# Sheet1.net
KiCad netlist of a schematic drawn in Altium Designer
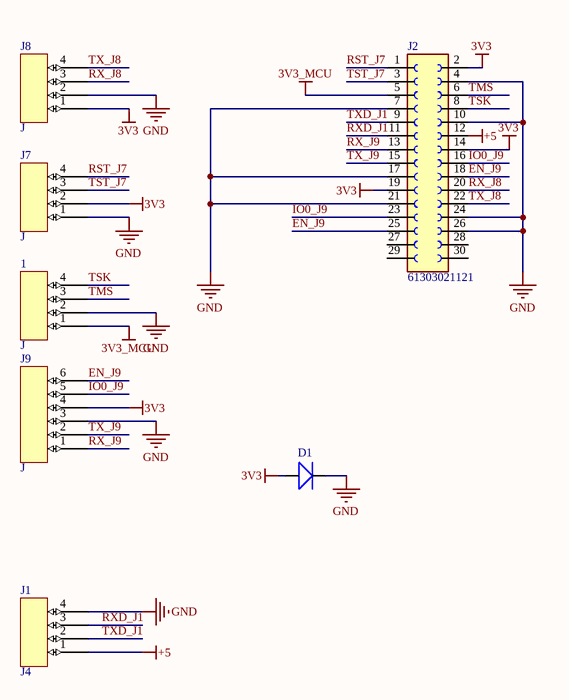
[diagram p0: Sheet1.SchDoc]

(export (version "E")
  (design (tool "Eeschema 10.0.6"))
  (components
    (comp (ref "1") (value "J") (footprint "J4") (libsource (lib "Schlib2") (part "J4")))
    (comp (ref "D1")
      (value "SMD-DIODE-SWITCHING-75V-150MA(D1206)")
      (footprint "LED-1206")
      (description "304040005")
      (fields (field (name "MF") "{'manufacturer': u'Bourns'}"))
      (libsource (lib "CD1206-S01575") (part "SMD-DIODE-SWITCHING-75V-150MA(D1206)"))
    )
    (comp (ref "J1") (value "J4") (footprint "J4") (libsource (lib "Schlib2") (part "J4")))
    (comp (ref "J2")
      (value "61303021121")
      (footprint "61303021121:61303021121")
      (fields (field (name "MF") "{'manufacturer': u'Wurth Elektronik'}"))
      (libsource (lib "*") (part "61303021121"))
    )
    (comp (ref "J7") (value "J") (footprint "J4") (libsource (lib "Schlib2") (part "J4")))
    (comp (ref "J8") (value "J") (footprint "J4") (libsource (lib "Schlib2") (part "J4")))
    (comp (ref "J9") (value "J") (footprint "J6") (libsource (lib "Schlib1") (part "J6")))
  )
  (nets
    (net (code "1") (name "+5") (class "Default")
      (node (ref "J1") (pin "1") (pintype "bidirectional"))
      (node (ref "J2") (pin "12") (pinfunction "25_12") (pintype "passive"))
    )
    (net (code "2") (name "/EN_J9") (class "Default")
      (node (ref "J2") (pin "18") (pinfunction "22_18") (pintype "passive"))
      (node (ref "J2") (pin "25") (pinfunction "13_25") (pintype "passive"))
      (node (ref "J9") (pin "6") (pintype "bidirectional"))
    )
    (net (code "3") (name "/IO0_J9") (class "Default")
      (node (ref "J2") (pin "16") (pinfunction "23_16") (pintype "passive"))
      (node (ref "J2") (pin "23") (pinfunction "12_23") (pintype "passive"))
      (node (ref "J9") (pin "5") (pintype "bidirectional"))
    )
    (net (code "4") (name "/RST_J7") (class "Default")
      (node (ref "J2") (pin "1") (pinfunction "1_1") (pintype "passive"))
      (node (ref "J7") (pin "4") (pintype "bidirectional"))
    )
    (net (code "5") (name "/RXD_J1") (class "Default")
      (node (ref "J1") (pin "3") (pintype "bidirectional"))
      (node (ref "J2") (pin "11") (pinfunction "6_11") (pintype "passive"))
    )
    (net (code "6") (name "/RX_J8") (class "Default")
      (node (ref "J2") (pin "20") (pinfunction "21_20") (pintype "passive"))
      (node (ref "J8") (pin "3") (pintype "bidirectional"))
    )
    (net (code "7") (name "/RX_J9") (class "Default")
      (node (ref "J2") (pin "13") (pinfunction "7_13") (pintype "passive"))
      (node (ref "J9") (pin "1") (pintype "bidirectional"))
    )
    (net (code "8") (name "/TMS") (class "Default")
      (node (ref "1") (pin "3") (pintype "bidirectional"))
      (node (ref "J2") (pin "6") (pinfunction "28_6") (pintype "passive"))
    )
    (net (code "9") (name "/TSK") (class "Default")
      (node (ref "1") (pin "4") (pintype "bidirectional"))
      (node (ref "J2") (pin "8") (pinfunction "27_8") (pintype "passive"))
    )
    (net (code "10") (name "/TST_J7") (class "Default")
      (node (ref "J2") (pin "3") (pinfunction "2_3") (pintype "passive"))
      (node (ref "J7") (pin "3") (pintype "bidirectional"))
    )
    (net (code "11") (name "/TXD_J1") (class "Default")
      (node (ref "J1") (pin "2") (pintype "bidirectional"))
      (node (ref "J2") (pin "9") (pinfunction "5_9") (pintype "passive"))
    )
    (net (code "12") (name "/TX_J8") (class "Default")
      (node (ref "J2") (pin "22") (pinfunction "20_22") (pintype "passive"))
      (node (ref "J8") (pin "4") (pintype "bidirectional"))
    )
    (net (code "13") (name "/TX_J9") (class "Default")
      (node (ref "J2") (pin "15") (pinfunction "8_15") (pintype "passive"))
      (node (ref "J9") (pin "2") (pintype "bidirectional"))
    )
    (net (code "14") (name "3V3") (class "Default")
      (node (ref "D1") (pin "POS") (pinfunction "POS_POS") (pintype "passive"))
      (node (ref "J2") (pin "14") (pinfunction "24_14") (pintype "passive"))
      (node (ref "J2") (pin "19") (pinfunction "10_19") (pintype "passive"))
      (node (ref "J2") (pin "2") (pinfunction "30_2") (pintype "passive"))
      (node (ref "J7") (pin "2") (pintype "bidirectional"))
      (node (ref "J8") (pin "1") (pintype "bidirectional"))
      (node (ref "J9") (pin "4") (pintype "bidirectional"))
    )
    (net (code "15") (name "3V3_MCU") (class "Default")
      (node (ref "1") (pin "1") (pintype "bidirectional"))
      (node (ref "J2") (pin "5") (pinfunction "3_5") (pintype "passive"))
    )
    (net (code "16") (name "GND") (class "Default")
      (node (ref "1") (pin "2") (pintype "bidirectional"))
      (node (ref "D1") (pin "NEG") (pinfunction "NEG_NEG") (pintype "passive"))
      (node (ref "J1") (pin "4") (pintype "bidirectional"))
      (node (ref "J2") (pin "10") (pinfunction "26_10") (pintype "passive"))
      (node (ref "J2") (pin "17") (pinfunction "9_17") (pintype "passive"))
      (node (ref "J2") (pin "21") (pinfunction "11_21") (pintype "passive"))
      (node (ref "J2") (pin "24") (pinfunction "19_24") (pintype "passive"))
      (node (ref "J2") (pin "26") (pinfunction "18_26") (pintype "passive"))
      (node (ref "J2") (pin "4") (pinfunction "29_4") (pintype "passive"))
      (node (ref "J2") (pin "7") (pinfunction "4_7") (pintype "passive"))
      (node (ref "J7") (pin "1") (pintype "bidirectional"))
      (node (ref "J8") (pin "2") (pintype "bidirectional"))
      (node (ref "J9") (pin "3") (pintype "bidirectional"))
    )
    (net (code "17") (name "unconnected-(J2-14-Pad27)") (class "Default")
      (node (ref "J2") (pin "27") (pinfunction "14_27") (pintype "passive"))
    )
    (net (code "18") (name "unconnected-(J2-15-Pad29)") (class "Default")
      (node (ref "J2") (pin "29") (pinfunction "15_29") (pintype "passive"))
    )
    (net (code "19") (name "unconnected-(J2-16-Pad30)") (class "Default")
      (node (ref "J2") (pin "30") (pinfunction "16_30") (pintype "passive"))
    )
    (net (code "20") (name "unconnected-(J2-17-Pad28)") (class "Default")
      (node (ref "J2") (pin "28") (pinfunction "17_28") (pintype "passive"))
    )
  )
)
